# LCL_prec_5V.net
KiCad netlist of a schematic drawn in Altium Designer
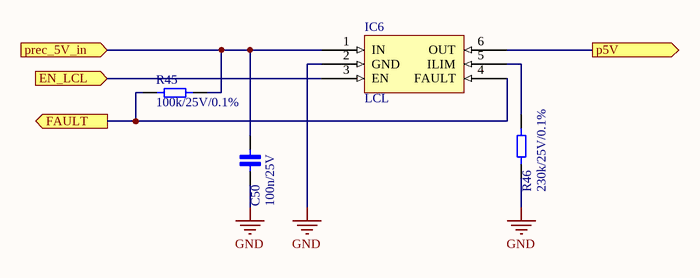
[diagram p0: LCL_prec_5V.SchDoc]

(export (version "E")
  (design (tool "Eeschema 10.0.6"))
  (components
    (comp (ref "C50")
      (value "100n/25V")
      (footprint "CAP_0603")
      (description "Ceramic Capacitor 100n / 0603 / 25V / ±5%, Wurth Elektronik MLCC")
      (libsource (lib "Cubesat_lib") (part "Cap_0603_100n"))
    )
    (comp (ref "IC6")
      (value "LCL")
      (footprint "SOT-23-6")
      (description "Latch-off Current Limiter")
      (libsource (lib "Cubesat_lib") (part "TPS2553"))
    )
    (comp (ref "R45")
      (value "100k/25V/0.1%")
      (footprint "RES_0603")
      (description "Vishay, thin film resistor 100k/25V/0.1%")
      (libsource (lib "Cubesat_lib") (part "Res_0603_100k"))
    )
    (comp (ref "R46")
      (value "230k/25V/0.1%")
      (footprint "RES_0603")
      (description "Vishay, thin film resistor 230k/25V/0.1%")
      (libsource (lib "Cubesat_lib") (part "Res_0603_230k"))
    )
  )
  (nets
    (net (code "1") (name "/EN_LCL") (class "Default")
      (node (ref "IC6") (pin "3") (pinfunction "EN_3") (pintype "input"))
    )
    (net (code "2") (name "/FAULT") (class "Default")
      (node (ref "IC6") (pin "4") (pinfunction "FAULT_4") (pintype "input"))
      (node (ref "R45") (pin "2") (pinfunction "2_2") (pintype "passive"))
    )
    (net (code "3") (name "/p5V") (class "Default")
      (node (ref "IC6") (pin "6") (pinfunction "OUT_6") (pintype "input"))
    )
    (net (code "4") (name "/prec_5V_in") (class "Default")
      (node (ref "C50") (pin "2") (pinfunction "2_2") (pintype "passive"))
      (node (ref "IC6") (pin "1") (pinfunction "IN_1") (pintype "input"))
      (node (ref "R45") (pin "2") (pinfunction "2_2") (pintype "passive"))
    )
    (net (code "5") (name "GND") (class "Default")
      (node (ref "C50") (pin "2") (pinfunction "2_2") (pintype "passive"))
      (node (ref "IC6") (pin "2") (pinfunction "GND_2") (pintype "input"))
      (node (ref "R46") (pin "2") (pinfunction "2_2") (pintype "passive"))
    )
    (net (code "6") (name "Net-(IC6-ILIM)") (class "Default")
      (node (ref "IC6") (pin "5") (pinfunction "ILIM_5") (pintype "input"))
      (node (ref "R46") (pin "2") (pinfunction "2_2") (pintype "passive"))
    )
  )
)
